# openSX70_MEROE_V7_20190604_TSL235.net
KiCad netlist of a schematic drawn in EAGLE
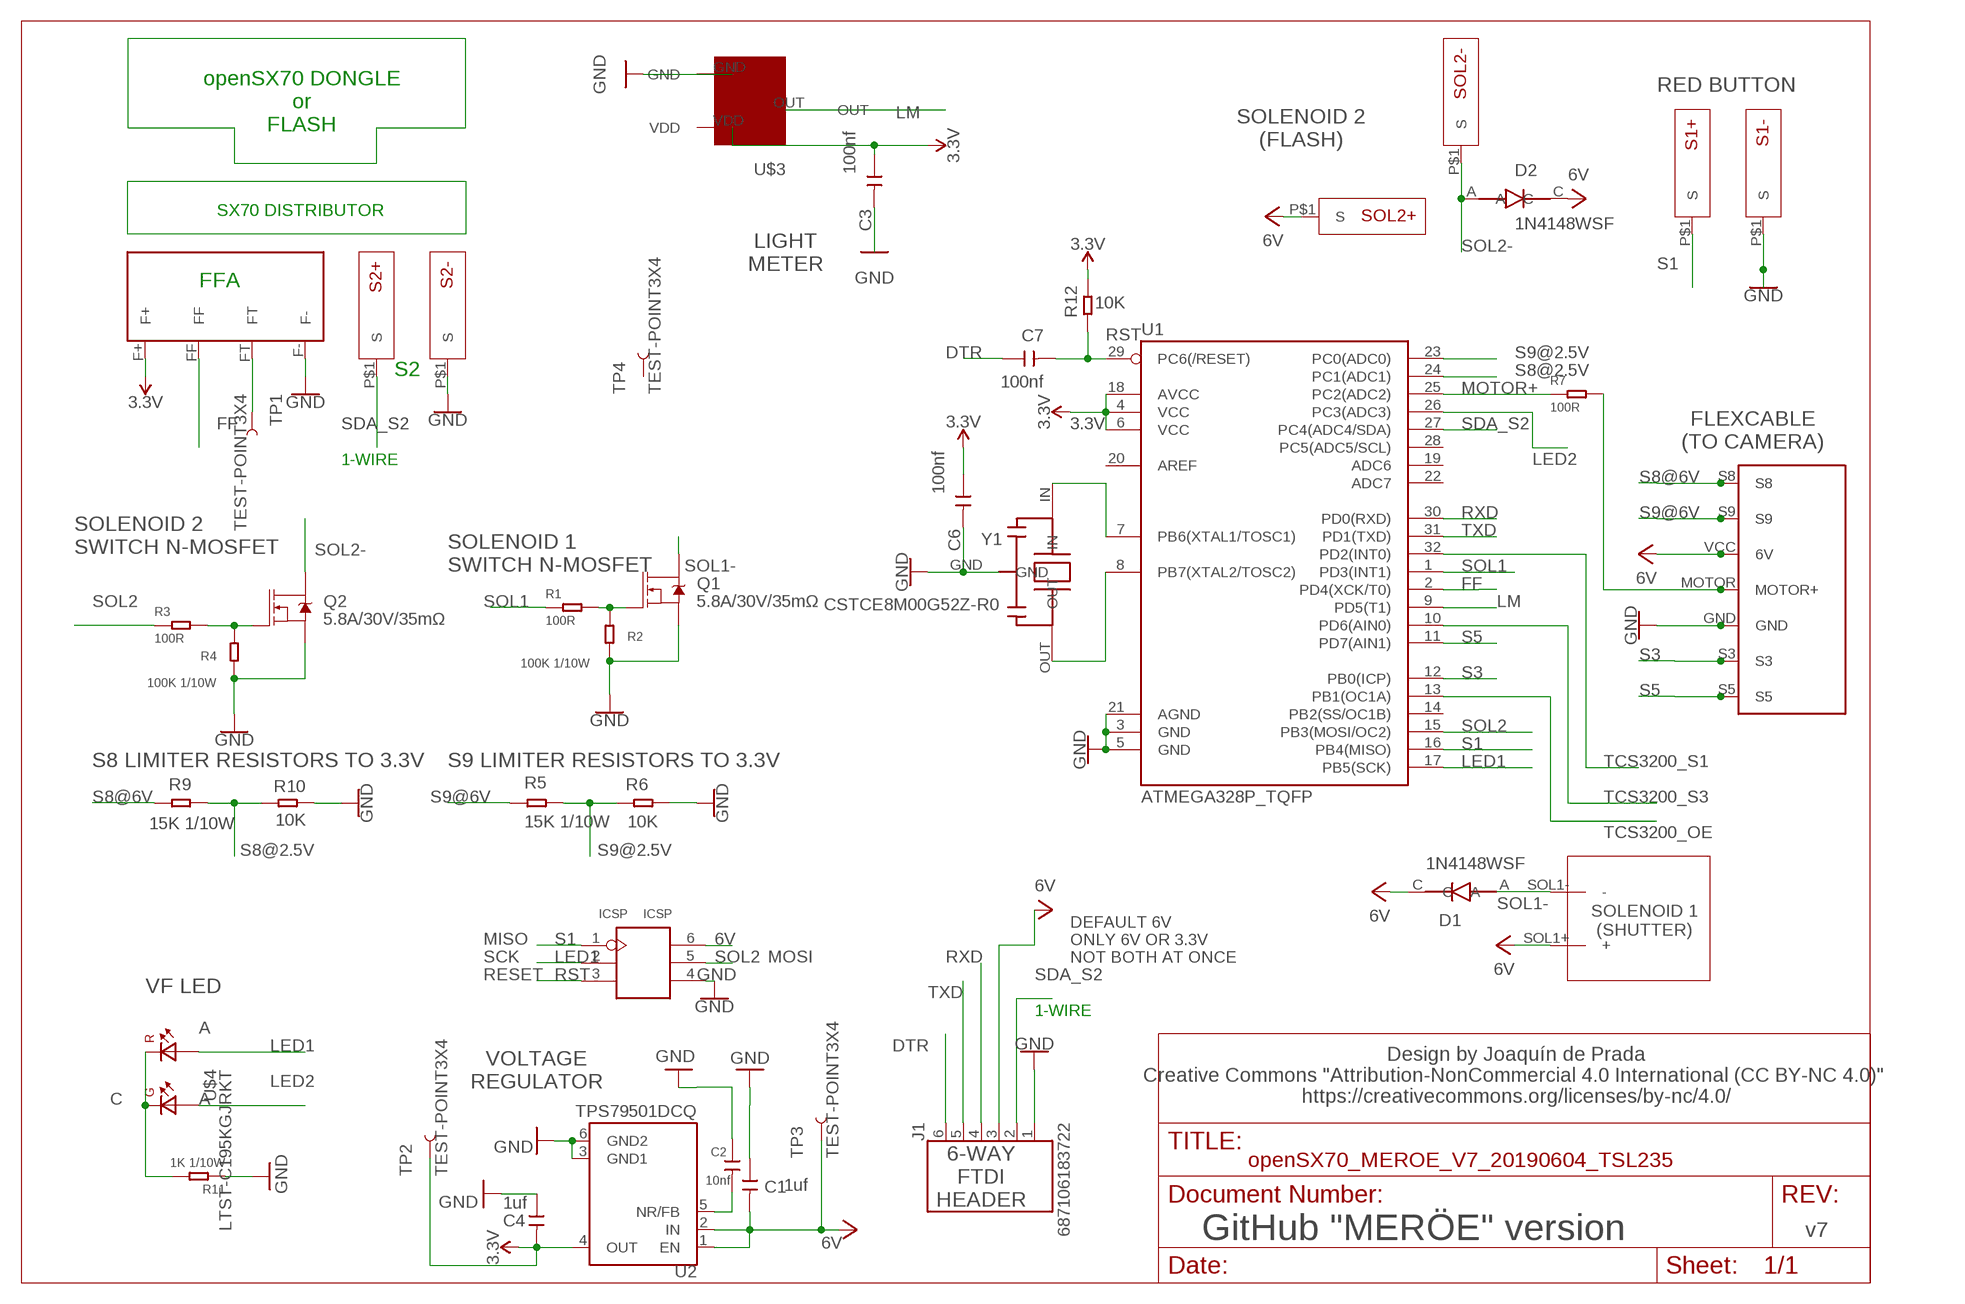
[diagram p0: schematic, sheet 1]

(export (version "E")
  (design (tool "Eeschema 10.0.6"))
  (components
    (comp (ref "C1")
      (value "1uf")
      (footprint "eagle-import:C0603")
      (fields (field (name "MPN") "CC0603KRX5R6BB106"))
      (libsource (lib "eagle-import") (part "CERAMIC-10UF-10V-10%-X5R(0603)"))
    )
    (comp (ref "C2")
      (value "10nf")
      (footprint "eagle-import:C0603")
      (fields (field (name "MPN") "CC0603KRX7R9BB104"))
      (libsource (lib "eagle-import") (part "CERAMIC-100NF-50V-10%-X7R(0603)"))
    )
    (comp (ref "C3")
      (value "100nf")
      (footprint "eagle-import:C0603")
      (fields (field (name "MPN") "CC0603KRX7R9BB104"))
      (libsource (lib "eagle-import") (part "CERAMIC-100NF-50V-10%-X7R(0603)"))
    )
    (comp (ref "C4")
      (value "1uf")
      (footprint "eagle-import:C0603")
      (fields (field (name "MPN") "CC0603KRX5R6BB106"))
      (libsource (lib "eagle-import") (part "CERAMIC-10UF-10V-10%-X5R(0603)"))
    )
    (comp (ref "C6")
      (value "100nf")
      (footprint "eagle-import:C0603")
      (fields (field (name "MPN") "CC0603KRX7R9BB104"))
      (libsource (lib "eagle-import") (part "CERAMIC-100NF-50V-10%-X7R(0603)"))
    )
    (comp (ref "C7")
      (value "100nf")
      (footprint "eagle-import:C0603")
      (fields (field (name "MPN") "CC0603KRX7R9BB104"))
      (libsource (lib "eagle-import") (part "CERAMIC-100NF-50V-10%-X7R(0603)"))
    )
    (comp (ref "D1")
      (value "1N4148WSF")
      (footprint "eagle-import:SODFL2512X100N")
      (fields (field (name "MANUFACTURER") "Fairchild Semiconductor"))
      (libsource (lib "eagle-import") (part "1N4148WS"))
    )
    (comp (ref "D2")
      (value "1N4148WSF")
      (footprint "eagle-import:SODFL2512X100N")
      (fields (field (name "MANUFACTURER") "Fairchild Semiconductor"))
      (libsource (lib "eagle-import") (part "1N4148WS"))
    )
    (comp (ref "ICSP")
      (value "ICSP")
      (footprint "eagle-import:H2X3-2.54")
      (libsource (lib "eagle-import") (part "ICSP"))
    )
    (comp (ref "J1")
      (value "687106183722")
      (footprint "eagle-import:687106183722")
      (fields (field (name "MF") "Wurth Electronics"))
      (libsource (lib "eagle-import") (part "687106183722"))
    )
    (comp (ref "Q1")
      (value "5.8A/30V/35mΩ")
      (footprint "eagle-import:SOT23-3")
      (libsource (lib "eagle-import") (part "MOSFET-NCH-AO3404A"))
    )
    (comp (ref "Q2")
      (value "5.8A/30V/35mΩ")
      (footprint "eagle-import:SOT23-3")
      (libsource (lib "eagle-import") (part "MOSFET-NCH-AO3404A"))
    )
    (comp (ref "R1")
      (value "100R")
      (footprint "eagle-import:R0603")
      (fields (field (name "MPN") "RC0603JR-07100RL"))
      (libsource (lib "eagle-import") (part "SMD-RES-100R-5%-1/10W(0603)"))
    )
    (comp (ref "R2")
      (value "100K 1/10W")
      (footprint "eagle-import:R0603")
      (fields (field (name "MPN") "RC0603JR-07100KL"))
      (libsource (lib "eagle-import") (part "SMD-RES-100K-5%-1/10W(0603)"))
    )
    (comp (ref "R3")
      (value "100R")
      (footprint "eagle-import:R0603")
      (fields (field (name "MPN") "RC0603JR-07100RL"))
      (libsource (lib "eagle-import") (part "SMD-RES-100R-5%-1/10W(0603)"))
    )
    (comp (ref "R4")
      (value "100K 1/10W")
      (footprint "eagle-import:R0603")
      (fields (field (name "MPN") "RC0603JR-07100KL"))
      (libsource (lib "eagle-import") (part "SMD-RES-100K-5%-1/10W(0603)"))
    )
    (comp (ref "R5")
      (value "15K 1/10W")
      (footprint "eagle-import:R0603")
      (fields (field (name "MPN") "RC0603FR-0715KL"))
      (libsource (lib "eagle-import") (part "SMD-RES-15K-1%-1/10W(0603)"))
    )
    (comp (ref "R6")
      (value "10K")
      (footprint "eagle-import:R0603")
      (fields (field (name "MPN") "RC0603FR-0710KL"))
      (libsource (lib "eagle-import") (part "SMD-RES-10K-1%-1/10W(0603)"))
    )
    (comp (ref "R7")
      (value "100R")
      (footprint "eagle-import:R0603")
      (fields (field (name "MPN") "RC0603JR-07100RL"))
      (libsource (lib "eagle-import") (part "SMD-RES-100R-5%-1/10W(0603)"))
    )
    (comp (ref "R9")
      (value "15K 1/10W")
      (footprint "eagle-import:R0603")
      (fields (field (name "MPN") "RC0603FR-0715KL"))
      (libsource (lib "eagle-import") (part "SMD-RES-15K-1%-1/10W(0603)"))
    )
    (comp (ref "R10")
      (value "10K")
      (footprint "eagle-import:R0603")
      (fields (field (name "MPN") "RC0603FR-0710KL"))
      (libsource (lib "eagle-import") (part "SMD-RES-10K-1%-1/10W(0603)"))
    )
    (comp (ref "R11")
      (value "1K 1/10W")
      (footprint "eagle-import:R0603")
      (fields (field (name "MPN") "RC0603JR-071KL"))
      (libsource (lib "eagle-import") (part "SMD-RES-1K-5%-1/10W(0603)"))
    )
    (comp (ref "R12")
      (value "10K")
      (footprint "eagle-import:R0603")
      (fields (field (name "MPN") "RC0603FR-0710KL"))
      (libsource (lib "eagle-import") (part "SMD-RES-10K-1%-1/10W(0603)"))
    )
    (comp (ref "S1+")
      (value "SX70-S-PAD-NEW")
      (footprint "eagle-import:SX70-S-PAD2")
      (libsource (lib "eagle-import") (part "SX70-S-PAD-NEW"))
    )
    (comp (ref "S1-")
      (value "SX70-S-PAD-NEW")
      (footprint "eagle-import:SX70-S-PAD2")
      (libsource (lib "eagle-import") (part "SX70-S-PAD-NEW"))
    )
    (comp (ref "S2+")
      (value "SX70-S-PAD-NEW")
      (footprint "eagle-import:SX70-S-PAD2")
      (libsource (lib "eagle-import") (part "SX70-S-PAD-NEW"))
    )
    (comp (ref "S2-")
      (value "SX70-S-PAD-NEW")
      (footprint "eagle-import:SX70-S-PAD2")
      (libsource (lib "eagle-import") (part "SX70-S-PAD-NEW"))
    )
    (comp (ref "SOL1")
      (value "SX70-SOLENOID1-2PADS")
      (footprint "eagle-import:SX70-SOLENOID1-2")
      (libsource (lib "eagle-import") (part "SX70-SOLENOID1-2PADS"))
    )
    (comp (ref "SOL2+")
      (value "SX70-S-PAD-NEW")
      (footprint "eagle-import:SX70-S-PAD2")
      (libsource (lib "eagle-import") (part "SX70-S-PAD-NEW"))
    )
    (comp (ref "SOL2-")
      (value "SX70-S-PAD-NEW")
      (footprint "eagle-import:SX70-S-PAD2")
      (libsource (lib "eagle-import") (part "SX70-S-PAD-NEW"))
    )
    (comp (ref "TP1")
      (value "TEST-POINT3X4")
      (footprint "eagle-import:PAD.03X.04")
      (libsource (lib "eagle-import") (part "TEST-POINT3X4"))
    )
    (comp (ref "TP2")
      (value "TEST-POINT3X4")
      (footprint "eagle-import:PAD.03X.04")
      (libsource (lib "eagle-import") (part "TEST-POINT3X4"))
    )
    (comp (ref "TP3")
      (value "TEST-POINT3X4")
      (footprint "eagle-import:PAD.03X.04")
      (libsource (lib "eagle-import") (part "TEST-POINT3X4"))
    )
    (comp (ref "TP4")
      (value "TEST-POINT3X4")
      (footprint "eagle-import:PAD.03X.04")
      (libsource (lib "eagle-import") (part "TEST-POINT3X4"))
    )
    (comp (ref "U$1")
      (value "SX70-7-PAD")
      (footprint "eagle-import:SX70-7-PAD-PROPER")
      (libsource (lib "eagle-import") (part "SX70-7-PAD"))
    )
    (comp (ref "U$2")
      (value "FFA")
      (footprint "eagle-import:FFA-PAD-PACKAGE")
      (libsource (lib "eagle-import") (part "SX70-FFA-PAD"))
    )
    (comp (ref "U$3")
      (value "TSL235R")
      (footprint "eagle-import:TSL235R")
      (libsource (lib "eagle-import") (part "TSL235R"))
    )
    (comp (ref "U$4")
      (value "LTST-C195KGJRKT")
      (footprint "eagle-import:LTST-BILED-15X16")
      (fields (field (name "MF") "Lite-On Inc."))
      (libsource (lib "eagle-import") (part "LTST-C195KGJRKT"))
    )
    (comp (ref "U1")
      (value "ATMEGA328P_TQFP")
      (footprint "eagle-import:TQFP32-08")
      (libsource (lib "eagle-import") (part "ATMEGA328P_TQFP"))
    )
    (comp (ref "U2")
      (value "TPS79501DCQ")
      (footprint "eagle-import:SOT127P706X180-6N")
      (fields (field (name "MF") "Texas Instruments"))
      (libsource (lib "eagle-import") (part "TPS79501DCQ"))
    )
    (comp (ref "Y1")
      (value "CSTCE8M00G52Z-R0")
      (footprint "eagle-import:CFP95P160X100-3N")
      (fields (field (name "MF") "Murata") (field (name "MP") "CSTCE16M0V53-R0"))
      (libsource (lib "eagle-import") (part "CSTCE16M0V53-R0"))
    )
  )
  (nets
    (net (code "1") (name "/DTR") (class "Default")
      (node (ref "C7") (pin "1") (pinfunction "1_1") (pintype "passive"))
      (node (ref "J1") (pin "6") (pinfunction "1_6") (pintype "passive"))
    )
    (net (code "2") (name "/FF") (class "Default")
      (node (ref "U$2") (pin "FF") (pinfunction "FF_FF") (pintype "bidirectional"))
      (node (ref "U1") (pin "2") (pinfunction "PD4(XCK/T0)_2") (pintype "bidirectional"))
    )
    (net (code "3") (name "/LED1") (class "Default")
      (node (ref "ICSP") (pin "2") (pinfunction "SCK_2") (pintype "bidirectional"))
      (node (ref "U$4") (pin "P$2") (pinfunction "A2_P$2") (pintype "passive"))
      (node (ref "U1") (pin "17") (pinfunction "PB5(SCK)_17") (pintype "bidirectional"))
    )
    (net (code "4") (name "/LED2") (class "Default")
      (node (ref "U$4") (pin "P$1") (pinfunction "A1_P$1") (pintype "passive"))
      (node (ref "U1") (pin "26") (pinfunction "PC3(ADC3)_26") (pintype "bidirectional"))
    )
    (net (code "5") (name "/LM") (class "Default")
      (node (ref "U$3") (pin "OUT") (pinfunction "OUT_OUT") (pintype "bidirectional"))
      (node (ref "U1") (pin "9") (pinfunction "PD5(T1)_9") (pintype "bidirectional"))
    )
    (net (code "6") (name "/MOTOR+") (class "Default")
      (node (ref "R7") (pin "1") (pinfunction "1_1") (pintype "passive"))
      (node (ref "U1") (pin "25") (pinfunction "PC2(ADC2)_25") (pintype "bidirectional"))
    )
    (net (code "7") (name "/RST") (class "Default")
      (node (ref "C7") (pin "2") (pinfunction "2_2") (pintype "passive"))
      (node (ref "ICSP") (pin "3") (pinfunction "RST_3") (pintype "bidirectional"))
      (node (ref "R12") (pin "1") (pinfunction "1_1") (pintype "passive"))
      (node (ref "U1") (pin "29") (pinfunction "PC6(/RESET)_29") (pintype "bidirectional"))
    )
    (net (code "8") (name "/RXD") (class "Default")
      (node (ref "J1") (pin "4") (pinfunction "3_4") (pintype "passive"))
      (node (ref "U1") (pin "30") (pinfunction "PD0(RXD)_30") (pintype "bidirectional"))
    )
    (net (code "9") (name "/S1") (class "Default")
      (node (ref "ICSP") (pin "1") (pinfunction "MISO_1") (pintype "bidirectional"))
      (node (ref "S1+") (pin "P$1") (pinfunction "S_P$1") (pintype "bidirectional"))
      (node (ref "U1") (pin "16") (pinfunction "PB4(MISO)_16") (pintype "bidirectional"))
    )
    (net (code "10") (name "/S3") (class "Default")
      (node (ref "U$1") (pin "S3") (pinfunction "S3_S3") (pintype "bidirectional"))
      (node (ref "U1") (pin "12") (pinfunction "PB0(ICP)_12") (pintype "bidirectional"))
    )
    (net (code "11") (name "/S5") (class "Default")
      (node (ref "U$1") (pin "S5") (pinfunction "S5_S5") (pintype "bidirectional"))
      (node (ref "U1") (pin "11") (pinfunction "PD7(AIN1)_11") (pintype "bidirectional"))
    )
    (net (code "12") (name "/S8@2.5V") (class "Default")
      (node (ref "R10") (pin "1") (pinfunction "1_1") (pintype "passive"))
      (node (ref "R9") (pin "2") (pinfunction "2_2") (pintype "passive"))
      (node (ref "U1") (pin "24") (pinfunction "PC1(ADC1)_24") (pintype "bidirectional"))
    )
    (net (code "13") (name "/S8@6V") (class "Default")
      (node (ref "R9") (pin "1") (pinfunction "1_1") (pintype "passive"))
      (node (ref "U$1") (pin "S8") (pinfunction "S8_S8") (pintype "bidirectional"))
    )
    (net (code "14") (name "/S9@2.5V") (class "Default")
      (node (ref "R5") (pin "2") (pinfunction "2_2") (pintype "passive"))
      (node (ref "R6") (pin "1") (pinfunction "1_1") (pintype "passive"))
      (node (ref "U1") (pin "23") (pinfunction "PC0(ADC0)_23") (pintype "bidirectional"))
    )
    (net (code "15") (name "/S9@6V") (class "Default")
      (node (ref "R5") (pin "1") (pinfunction "1_1") (pintype "passive"))
      (node (ref "U$1") (pin "S9") (pinfunction "S9_S9") (pintype "bidirectional"))
    )
    (net (code "16") (name "/SDA_S2") (class "Default")
      (node (ref "J1") (pin "2") (pinfunction "5_2") (pintype "passive"))
      (node (ref "S2+") (pin "P$1") (pinfunction "S_P$1") (pintype "bidirectional"))
      (node (ref "U1") (pin "27") (pinfunction "PC4(ADC4/SDA)_27") (pintype "bidirectional"))
    )
    (net (code "17") (name "/SOL1") (class "Default")
      (node (ref "R1") (pin "1") (pinfunction "1_1") (pintype "passive"))
      (node (ref "U1") (pin "1") (pinfunction "PD3(INT1)_1") (pintype "bidirectional"))
    )
    (net (code "18") (name "/SOL1-") (class "Default")
      (node (ref "D1") (pin "A") (pinfunction "A_A") (pintype "passive"))
      (node (ref "Q1") (pin "3") (pinfunction "D_3") (pintype "bidirectional"))
      (node (ref "SOL1") (pin "SOL1-") (pinfunction "-_SOL1-") (pintype "bidirectional"))
    )
    (net (code "19") (name "/SOL2") (class "Default")
      (node (ref "ICSP") (pin "5") (pinfunction "MOSI_5") (pintype "bidirectional"))
      (node (ref "R3") (pin "1") (pinfunction "1_1") (pintype "passive"))
      (node (ref "U1") (pin "15") (pinfunction "PB3(MOSI/OC2)_15") (pintype "bidirectional"))
    )
    (net (code "20") (name "/SOL2-") (class "Default")
      (node (ref "D2") (pin "A") (pinfunction "A_A") (pintype "passive"))
      (node (ref "Q2") (pin "3") (pinfunction "D_3") (pintype "bidirectional"))
      (node (ref "SOL2-") (pin "P$1") (pinfunction "S_P$1") (pintype "bidirectional"))
    )
    (net (code "21") (name "/TCS3200_OE") (class "Default")
      (node (ref "U1") (pin "13") (pinfunction "PB1(OC1A)_13") (pintype "bidirectional"))
    )
    (net (code "22") (name "/TCS3200_S1") (class "Default")
      (node (ref "U1") (pin "32") (pinfunction "PD2(INT0)_32") (pintype "bidirectional"))
    )
    (net (code "23") (name "/TCS3200_S3") (class "Default")
      (node (ref "U1") (pin "10") (pinfunction "PD6(AIN0)_10") (pintype "bidirectional"))
    )
    (net (code "24") (name "/TXD") (class "Default")
      (node (ref "J1") (pin "5") (pinfunction "2_5") (pintype "passive"))
      (node (ref "U1") (pin "31") (pinfunction "PD1(TXD)_31") (pintype "bidirectional"))
    )
    (net (code "25") (name "3.3V") (class "Default")
      (node (ref "C3") (pin "1") (pinfunction "1_1") (pintype "passive"))
      (node (ref "C4") (pin "2") (pinfunction "2_2") (pintype "passive"))
      (node (ref "C6") (pin "1") (pinfunction "1_1") (pintype "passive"))
      (node (ref "R12") (pin "2") (pinfunction "2_2") (pintype "passive"))
      (node (ref "TP2") (pin "P$1") (pinfunction "1_P$1") (pintype "bidirectional"))
      (node (ref "U$2") (pin "F+") (pinfunction "F+_F+") (pintype "bidirectional"))
      (node (ref "U$3") (pin "VDD") (pinfunction "VDD_VDD") (pintype "bidirectional"))
      (node (ref "U1") (pin "18") (pinfunction "AVCC_18") (pintype "bidirectional"))
      (node (ref "U1") (pin "4") (pinfunction "VCC_4") (pintype "bidirectional"))
      (node (ref "U1") (pin "6") (pinfunction "VCC_6") (pintype "bidirectional"))
      (node (ref "U2") (pin "4") (pinfunction "OUT_4") (pintype "output"))
    )
    (net (code "26") (name "6V") (class "Default")
      (node (ref "C1") (pin "2") (pinfunction "2_2") (pintype "passive"))
      (node (ref "D1") (pin "C") (pinfunction "C_C") (pintype "passive"))
      (node (ref "D2") (pin "C") (pinfunction "C_C") (pintype "passive"))
      (node (ref "ICSP") (pin "6") (pinfunction "VCC_6") (pintype "bidirectional"))
      (node (ref "J1") (pin "3") (pinfunction "4_3") (pintype "passive"))
      (node (ref "SOL1") (pin "SOL1+") (pinfunction "+_SOL1+") (pintype "bidirectional"))
      (node (ref "SOL2+") (pin "P$1") (pinfunction "S_P$1") (pintype "bidirectional"))
      (node (ref "TP3") (pin "P$1") (pinfunction "1_P$1") (pintype "bidirectional"))
      (node (ref "U$1") (pin "VCC") (pinfunction "6V_VCC") (pintype "bidirectional"))
      (node (ref "U2") (pin "1") (pinfunction "EN_1") (pintype "input"))
      (node (ref "U2") (pin "2") (pinfunction "IN_2") (pintype "input"))
    )
    (net (code "27") (name "GND") (class "Default")
      (node (ref "C1") (pin "1") (pinfunction "1_1") (pintype "passive"))
      (node (ref "C2") (pin "1") (pinfunction "1_1") (pintype "passive"))
      (node (ref "C3") (pin "2") (pinfunction "2_2") (pintype "passive"))
      (node (ref "C4") (pin "1") (pinfunction "1_1") (pintype "passive"))
      (node (ref "C6") (pin "2") (pinfunction "2_2") (pintype "passive"))
      (node (ref "ICSP") (pin "4") (pinfunction "GND_4") (pintype "bidirectional"))
      (node (ref "J1") (pin "1") (pinfunction "6_1") (pintype "passive"))
      (node (ref "Q1") (pin "2") (pinfunction "S_2") (pintype "bidirectional"))
      (node (ref "Q2") (pin "2") (pinfunction "S_2") (pintype "bidirectional"))
      (node (ref "R10") (pin "2") (pinfunction "2_2") (pintype "passive"))
      (node (ref "R11") (pin "1") (pinfunction "1_1") (pintype "passive"))
      (node (ref "R2") (pin "1") (pinfunction "1_1") (pintype "passive"))
      (node (ref "R4") (pin "1") (pinfunction "1_1") (pintype "passive"))
      (node (ref "R6") (pin "2") (pinfunction "2_2") (pintype "passive"))
      (node (ref "S1-") (pin "P$1") (pinfunction "S_P$1") (pintype "bidirectional"))
      (node (ref "S2-") (pin "P$1") (pinfunction "S_P$1") (pintype "bidirectional"))
      (node (ref "U$1") (pin "GND") (pinfunction "GND_GND") (pintype "bidirectional"))
      (node (ref "U$2") (pin "F-") (pinfunction "F-_F-") (pintype "bidirectional"))
      (node (ref "U$3") (pin "GND") (pinfunction "GND_GND") (pintype "bidirectional"))
      (node (ref "U1") (pin "21") (pinfunction "AGND_21") (pintype "bidirectional"))
      (node (ref "U1") (pin "3") (pinfunction "GND_3") (pintype "bidirectional"))
      (node (ref "U1") (pin "5") (pinfunction "GND_5") (pintype "bidirectional"))
      (node (ref "U2") (pin "3") (pinfunction "GND1_3") (pintype "power_in"))
      (node (ref "U2") (pin "6") (pinfunction "GND2_6") (pintype "power_in"))
      (node (ref "Y1") (pin "GND") (pinfunction "GND_GND") (pintype "passive"))
    )
    (net (code "28") (name "Net-(Q1-G)") (class "Default")
      (node (ref "Q1") (pin "1") (pinfunction "G_1") (pintype "bidirectional"))
      (node (ref "R1") (pin "2") (pinfunction "2_2") (pintype "passive"))
      (node (ref "R2") (pin "2") (pinfunction "2_2") (pintype "passive"))
    )
    (net (code "29") (name "Net-(Q2-G)") (class "Default")
      (node (ref "Q2") (pin "1") (pinfunction "G_1") (pintype "bidirectional"))
      (node (ref "R3") (pin "2") (pinfunction "2_2") (pintype "passive"))
      (node (ref "R4") (pin "2") (pinfunction "2_2") (pintype "passive"))
    )
    (net (code "30") (name "Net-(TP1-1)") (class "Default")
      (node (ref "TP1") (pin "P$1") (pinfunction "1_P$1") (pintype "bidirectional"))
      (node (ref "U$2") (pin "FT") (pinfunction "FT_FT") (pintype "bidirectional"))
    )
    (net (code "31") (name "Net-(U$1-MOTOR+)") (class "Default")
      (node (ref "R7") (pin "2") (pinfunction "2_2") (pintype "passive"))
      (node (ref "U$1") (pin "MOTOR") (pinfunction "MOTOR+_MOTOR") (pintype "bidirectional"))
    )
    (net (code "32") (name "Net-(U$4-K1)") (class "Default")
      (node (ref "R11") (pin "2") (pinfunction "2_2") (pintype "passive"))
      (node (ref "U$4") (pin "P$3") (pinfunction "K1_P$3") (pintype "passive"))
      (node (ref "U$4") (pin "P$4") (pinfunction "K2_P$4") (pintype "passive"))
    )
    (net (code "33") (name "Net-(U1-PB6(XTAL1{slash}TOSC1))") (class "Default")
      (node (ref "U1") (pin "7") (pinfunction "PB6(XTAL1/TOSC1)_7") (pintype "bidirectional"))
      (node (ref "Y1") (pin "IN") (pinfunction "IN_IN") (pintype "input"))
    )
    (net (code "34") (name "Net-(U1-PB7(XTAL2{slash}TOSC2))") (class "Default")
      (node (ref "U1") (pin "8") (pinfunction "PB7(XTAL2/TOSC2)_8") (pintype "bidirectional"))
      (node (ref "Y1") (pin "OUT") (pinfunction "OUT_OUT") (pintype "output"))
    )
    (net (code "35") (name "Net-(U2-NR{slash}FB)") (class "Default")
      (node (ref "C2") (pin "2") (pinfunction "2_2") (pintype "passive"))
      (node (ref "U2") (pin "5") (pinfunction "NR/FB_5") (pintype "input"))
    )
    (net (code "36") (name "unconnected-(TP4-1-PadP$1)") (class "Default")
      (node (ref "TP4") (pin "P$1") (pinfunction "1_P$1") (pintype "bidirectional"))
    )
    (net (code "37") (name "unconnected-(U1-ADC6-Pad19)") (class "Default")
      (node (ref "U1") (pin "19") (pinfunction "ADC6_19") (pintype "bidirectional"))
    )
    (net (code "38") (name "unconnected-(U1-ADC7-Pad22)") (class "Default")
      (node (ref "U1") (pin "22") (pinfunction "ADC7_22") (pintype "bidirectional"))
    )
    (net (code "39") (name "unconnected-(U1-AREF-Pad20)") (class "Default")
      (node (ref "U1") (pin "20") (pinfunction "AREF_20") (pintype "bidirectional"))
    )
    (net (code "40") (name "unconnected-(U1-PB2(SS{slash}OC1B)-Pad14)") (class "Default")
      (node (ref "U1") (pin "14") (pinfunction "PB2(SS/OC1B)_14") (pintype "bidirectional"))
    )
    (net (code "41") (name "unconnected-(U1-PC5(ADC5{slash}SCL)-Pad28)") (class "Default")
      (node (ref "U1") (pin "28") (pinfunction "PC5(ADC5/SCL)_28") (pintype "bidirectional"))
    )
  )
)
